# Relay.net
KiCad netlist of a schematic drawn in Altium Designer
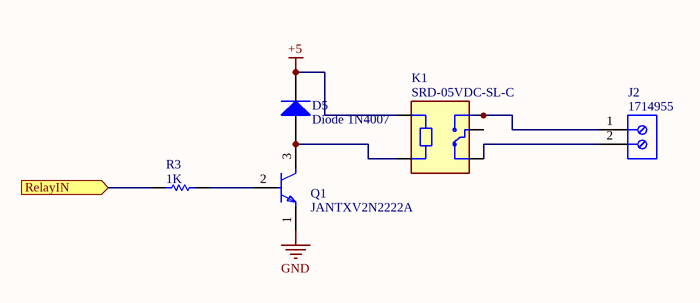
[diagram p0: Relay.SchDoc]

(export (version "E")
  (design (tool "Eeschema 10.0.6"))
  (components
    (comp (ref "D5")
      (value "Diode 1N4007")
      (footprint "DO-41")
      (description "1 Amp General Purpose Rectifier")
      (fields (field (name "PUBLISHER") "Altium Limited"))
      (libsource (lib "Miscellaneous Devices") (part "Diode 1N4007"))
    )
    (comp (ref "J2")
      (value "1714955")
      (footprint "PHOE-1714955_V")
      (description "PC Terminal Block, Pitch 6.35 mm, 1 x 2 Position, Height 21.5 mm, Tail Lenght 5.1 mm, RoHS, Bulk")
      (fields (field (name "MANUFACTURER") "Phoenix Contact"))
      (libsource (lib "Altium Content Vault") (part "CN-1P-F-TB2"))
    )
    (comp (ref "K1")
      (value "SRD-05VDC-SL-C")
      (footprint "RELAY_SRD-05VDC-SL-C")
      (fields (field (name "MF") "Songle Relay"))
      (libsource (lib "SRD-05VDC-SL-C") (part "SRD-05VDC-SL-C"))
    )
    (comp (ref "Q1")
      (value "JANTXV2N2222A")
      (footprint "FP-TO-18-MFG")
      (libsource (lib "Altium Content Vault") (part "acac84805612edcd38d576ce092733c"))
    )
    (comp (ref "R3")
      (value "1K")
      (footprint "RESA60-630X240")
      (description "Axial Resistor, 10 KOhm, +/- 1%, 0.25 W, -55 to 155 degC, 2-Pin THD, RoHS, Bulk")
      (fields (field (name "TOLERANCE") "1%") (field (name "MANUFACTURER") "Yageo"))
      (libsource (lib "Altium Content Vault") (part "RES-2"))
    )
  )
  (nets
    (net (code "1") (name "+5") (class "Default")
      (node (ref "D5") (pin "2") (pinfunction "K_2") (pintype "passive"))
      (node (ref "K1") (pin "A1") (pinfunction "A1_A1") (pintype "passive"))
    )
    (net (code "2") (name "/RelayIN") (class "Default")
      (node (ref "R3") (pin "1") (pinfunction "1_1") (pintype "passive"))
    )
    (net (code "3") (name "GND") (class "Default")
      (node (ref "Q1") (pin "1") (pinfunction "E_1") (pintype "passive"))
    )
    (net (code "4") (name "Net-(D5-A)") (class "Default")
      (node (ref "D5") (pin "1") (pinfunction "A_1") (pintype "passive"))
      (node (ref "K1") (pin "A2") (pinfunction "A2_A2") (pintype "passive"))
      (node (ref "Q1") (pin "3") (pinfunction "C_3") (pintype "passive"))
    )
    (net (code "5") (name "Net-(J2-Pad1)") (class "Default")
      (node (ref "J2") (pin "1") (pinfunction "1_1") (pintype "passive"))
      (node (ref "K1") (pin "NO") (pinfunction "NO_NO") (pintype "passive"))
    )
    (net (code "6") (name "Net-(J2-Pad2)") (class "Default")
      (node (ref "J2") (pin "2") (pinfunction "2_2") (pintype "passive"))
      (node (ref "K1") (pin "NC") (pinfunction "NC_NC") (pintype "passive"))
    )
    (net (code "7") (name "Net-(Q1-B)") (class "Default")
      (node (ref "Q1") (pin "2") (pinfunction "B_2") (pintype "passive"))
      (node (ref "R3") (pin "2") (pinfunction "2_2") (pintype "passive"))
    )
    (net (code "8") (name "unconnected-(K1-PadCOM)") (class "Default")
      (node (ref "K1") (pin "COM") (pinfunction "COM_COM") (pintype "passive"))
    )
  )
)
